# DC_Motor_Speed.net
KiCad netlist of a schematic drawn in Altium Designer
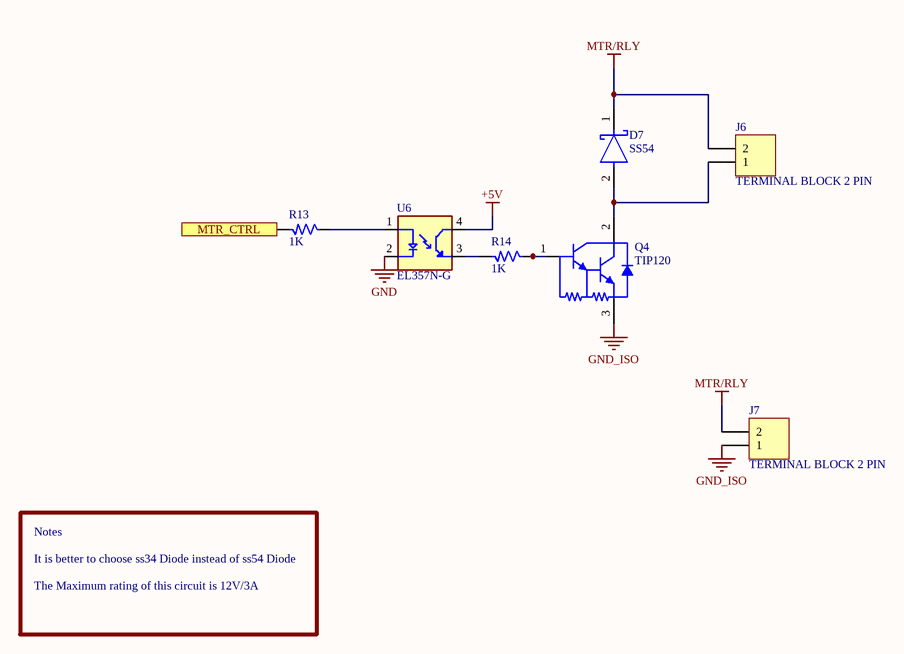
[diagram p0: DC Motor Speed.SchDoc]

(export (version "E")
  (design (tool "Eeschema 10.0.6"))
  (components
    (comp (ref "D7")
      (value "SS54")
      (footprint "FP-95400-MFG")
      (description "DIODE SCHOTTKY 40V 5A DO214AC")
      (libsource (lib "TAREKPCBLIB") (part "SS54-Schottky-40V-3A-DO214AC"))
    )
    (comp (ref "J6")
      (value "TERMINAL BLOCK 2 PIN")
      (footprint "CON2_P196_1729128_TH_ST")
      (description "2 Pins, 1 Row 5mm Pitch, straight Connector, male")
      (fields
        (field (name "MANUFACTURER") "Phoenix Contact")
        (field (name "MANUFACTURER PART NUMBER") "MKDSN1,5/2")
      )
      (libsource (lib "ESTEEMPCBLIB") (part "CON-TB_2X1-196-ST-TH"))
    )
    (comp (ref "J7")
      (value "TERMINAL BLOCK 2 PIN")
      (footprint "CON2_P196_1729128_TH_ST")
      (description "2 Pins, 1 Row 5mm Pitch, straight Connector, male")
      (fields
        (field (name "MANUFACTURER") "Phoenix Contact")
        (field (name "MANUFACTURER PART NUMBER") "MKDSN1,5/2")
      )
      (libsource (lib "ESTEEMPCBLIB") (part "CON-TB_2X1-196-ST-TH"))
    )
    (comp (ref "Q4")
      (value "TIP120")
      (footprint "ONSC-TO-220-3-221A-09")
      (description "Plastic Medium-Power, Complementary Silicon Transistor, 3-Pin TO-220, Tube")
      (fields (field (name "MANUFACTURER") "On Semiconductor"))
      (libsource (lib "TAREKPCBLIB") (part "TIP120"))
    )
    (comp (ref "R13")
      (value "1K")
      (footprint "RES_0805")
      (description "1 kOhms ±1% 0.125W, 1/8W Chip Resistor 0805 (2012 Metric) Moisture Resistant Thick Film")
      (fields (field (name "MANUFACTURER") "Walsin") (field (name "MANUFACTURER PART NUMBER") "WR08X1001FTL"))
      (libsource (lib "ESTEEMPCBLIB") (part "RES_1K-0.125W-1%-0805"))
    )
    (comp (ref "R14")
      (value "1K")
      (footprint "RES_0805")
      (description "1 kOhms ±1% 0.125W, 1/8W Chip Resistor 0805 (2012 Metric) Moisture Resistant Thick Film")
      (fields (field (name "MANUFACTURER") "Walsin") (field (name "MANUFACTURER PART NUMBER") "WR08X1001FTL"))
      (libsource (lib "ESTEEMPCBLIB") (part "RES_1K-0.125W-1%-0805"))
    )
    (comp (ref "U6")
      (value "EL357N-G")
      (footprint "OPTO_EL357N-G")
      (description "PHOTOTRANSISTOR PHOTOCOUPLER")
      (libsource (lib "TAREKPCBLIB") (part "EL357N-G"))
    )
  )
  (nets
    (net (code "1") (name "+5V") (class "Default")
      (node (ref "U6") (pin "4") (pinfunction "CT_4") (pintype "passive"))
    )
    (net (code "2") (name "/MTR_CTRL") (class "Default")
      (node (ref "R13") (pin "2") (pinfunction "2_2") (pintype "passive"))
    )
    (net (code "3") (name "GND") (class "Default")
      (node (ref "U6") (pin "2") (pinfunction "C_2") (pintype "passive"))
    )
    (net (code "4") (name "GND_ISO") (class "Default")
      (node (ref "J7") (pin "1") (pinfunction "1_1") (pintype "passive"))
      (node (ref "Q4") (pin "3") (pinfunction "E_3") (pintype "passive"))
    )
    (net (code "5") (name "MTR{slash}RLY") (class "Default")
      (node (ref "D7") (pin "1") (pinfunction "C_1") (pintype "passive"))
      (node (ref "J6") (pin "2") (pinfunction "2_2") (pintype "passive"))
      (node (ref "J7") (pin "2") (pinfunction "2_2") (pintype "passive"))
    )
    (net (code "6") (name "Net-(D7-A)") (class "Default")
      (node (ref "D7") (pin "2") (pinfunction "A_2") (pintype "passive"))
      (node (ref "J6") (pin "1") (pinfunction "1_1") (pintype "passive"))
      (node (ref "Q4") (pin "2") (pinfunction "C_2") (pintype "passive"))
    )
    (net (code "7") (name "Net-(Q4-B)") (class "Default")
      (node (ref "Q4") (pin "1") (pinfunction "B_1") (pintype "passive"))
      (node (ref "R14") (pin "1") (pinfunction "1_1") (pintype "passive"))
    )
    (net (code "8") (name "Net-(U6-A)") (class "Default")
      (node (ref "R13") (pin "1") (pinfunction "1_1") (pintype "passive"))
      (node (ref "U6") (pin "1") (pinfunction "A_1") (pintype "passive"))
    )
    (net (code "9") (name "Net-(U6-ET)") (class "Default")
      (node (ref "R14") (pin "2") (pinfunction "2_2") (pintype "passive"))
      (node (ref "U6") (pin "3") (pinfunction "ET_3") (pintype "passive"))
    )
  )
)
